# SmartRock_EC_V3_2_1_AGU.net
KiCad netlist of a schematic drawn in EAGLE
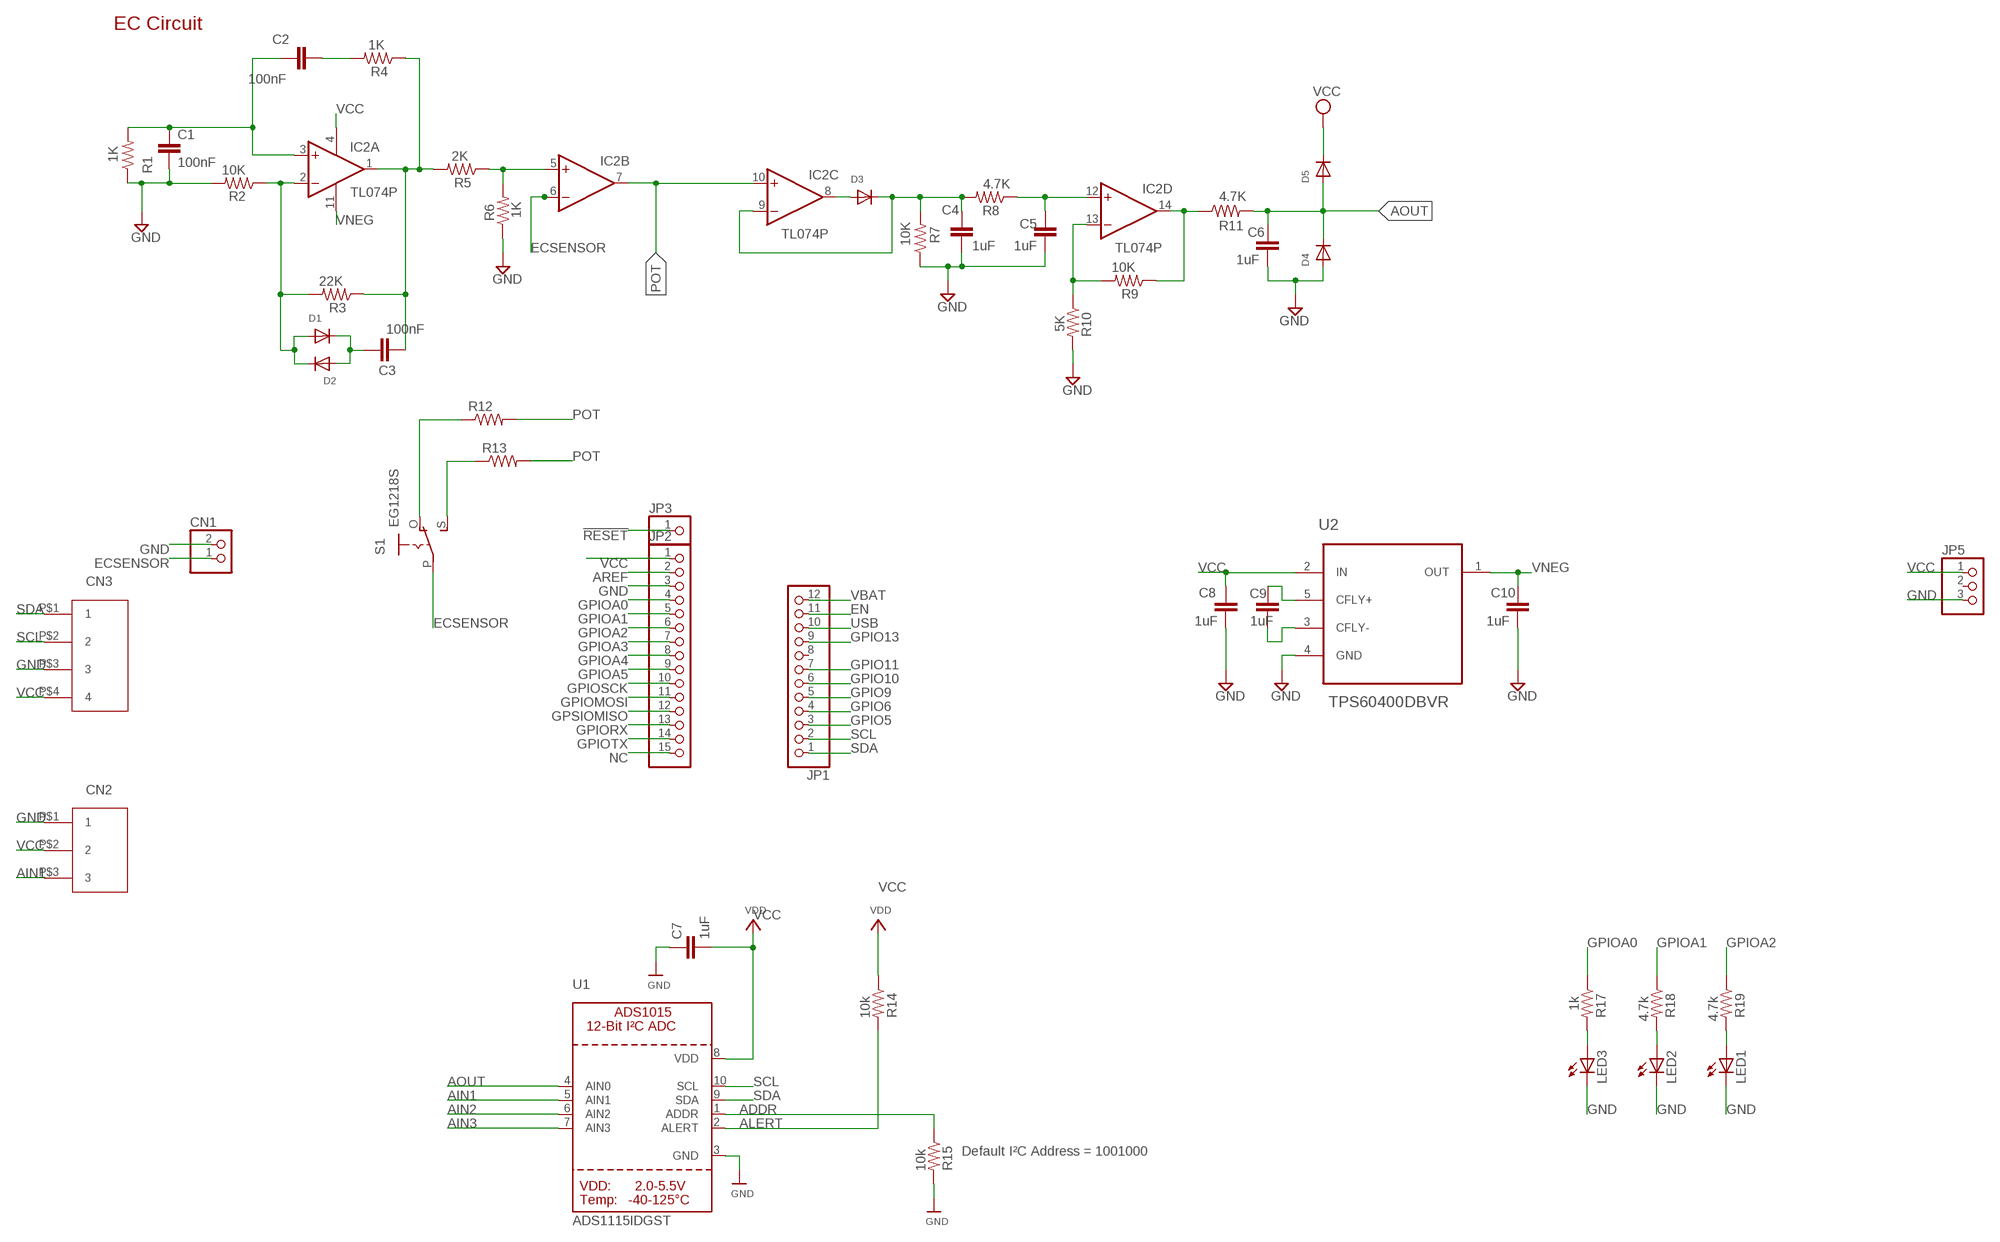
[diagram p0: schematic, sheet 1]

(export (version "E")
  (design (tool "Eeschema 10.0.6"))
  (components
    (comp (ref "C1")
      (value "100nF")
      (footprint "eagle-import:C1206")
      (libsource (lib "eagle-import") (part "C-EUC1206"))
    )
    (comp (ref "C2")
      (value "100nF")
      (footprint "eagle-import:C1206")
      (libsource (lib "eagle-import") (part "C-EUC1206"))
    )
    (comp (ref "C3")
      (value "100nF")
      (footprint "eagle-import:C1206")
      (libsource (lib "eagle-import") (part "C-EUC1206"))
    )
    (comp (ref "C4")
      (value "1uF")
      (footprint "eagle-import:C1206")
      (libsource (lib "eagle-import") (part "C-EUC1206"))
    )
    (comp (ref "C5")
      (value "1uF")
      (footprint "eagle-import:C1206")
      (libsource (lib "eagle-import") (part "C-EUC1206"))
    )
    (comp (ref "C6")
      (value "1uF")
      (footprint "eagle-import:C1206")
      (libsource (lib "eagle-import") (part "C-EUC1206"))
    )
    (comp (ref "C7")
      (value "1uF")
      (footprint "eagle-import:C1206")
      (libsource (lib "eagle-import") (part "C-EUC1206"))
    )
    (comp (ref "C8")
      (value "1uF")
      (footprint "eagle-import:C1206")
      (libsource (lib "eagle-import") (part "C-EUC1206"))
    )
    (comp (ref "C9")
      (value "1uF")
      (footprint "eagle-import:C1206")
      (libsource (lib "eagle-import") (part "C-EUC1206"))
    )
    (comp (ref "C10")
      (value "1uF")
      (footprint "eagle-import:C1206")
      (libsource (lib "eagle-import") (part "C-EUC1206"))
    )
    (comp (ref "CN1")
      (value "JST_2PIN-THM")
      (footprint "eagle-import:JST-PH-2-THM")
      (libsource (lib "eagle-import") (part "JST_2PIN-THM"))
    )
    (comp (ref "D1")
      (value "DIODEDO-1N4148")
      (footprint "eagle-import:DO-1N4148")
      (libsource (lib "eagle-import") (part "DIODEDO-1N4148"))
    )
    (comp (ref "D2")
      (value "DIODEDO-1N4148")
      (footprint "eagle-import:DO-1N4148")
      (libsource (lib "eagle-import") (part "DIODEDO-1N4148"))
    )
    (comp (ref "D3")
      (value "DIODEDO-1N4148")
      (footprint "eagle-import:DO-1N4148")
      (libsource (lib "eagle-import") (part "DIODEDO-1N4148"))
    )
    (comp (ref "D4")
      (value "DIODEDO-1N4148")
      (footprint "eagle-import:DO-1N4148")
      (libsource (lib "eagle-import") (part "DIODEDO-1N4148"))
    )
    (comp (ref "D5")
      (value "DIODEDO-1N4148")
      (footprint "eagle-import:DO-1N4148")
      (libsource (lib "eagle-import") (part "DIODEDO-1N4148"))
    )
    (comp (ref "IC2")
      (value "TL074P")
      (footprint "eagle-import:DIL14")
      (libsource (lib "eagle-import") (part "TL074P"))
    )
    (comp (ref "JP1")
      (value "PINHD-1X12-CB")
      (footprint "eagle-import:1X12-CB")
      (libsource (lib "eagle-import") (part "PINHD-1X12-CB"))
    )
    (comp (ref "JP2")
      (value "PINHD-1X15-CB")
      (footprint "eagle-import:1X15-CB")
      (libsource (lib "eagle-import") (part "PINHD-1X15-CB"))
    )
    (comp (ref "JP3")
      (value "PINHD-1X1CB")
      (footprint "eagle-import:1X01-CLEANBIG")
      (libsource (lib "eagle-import") (part "PINHD-1X1CB"))
    )
    (comp (ref "JP5")
      (value "PINHD-1X3CB")
      (footprint "eagle-import:1X03-CLEANBIG")
      (libsource (lib "eagle-import") (part "PINHD-1X3CB"))
    )
    (comp (ref "LED1")
      (value "LEDSMT1206")
      (footprint "eagle-import:1206")
      (libsource (lib "eagle-import") (part "LEDSMT1206"))
    )
    (comp (ref "LED2")
      (value "LEDSMT1206")
      (footprint "eagle-import:1206")
      (libsource (lib "eagle-import") (part "LEDSMT1206"))
    )
    (comp (ref "LED3")
      (value "LEDSMT1206")
      (footprint "eagle-import:1206")
      (libsource (lib "eagle-import") (part "LEDSMT1206"))
    )
    (comp (ref "R1")
      (value "1K")
      (footprint "eagle-import:R1206")
      (libsource (lib "eagle-import") (part "rcl_334_R-US_R1206"))
    )
    (comp (ref "R2")
      (value "10K")
      (footprint "eagle-import:R1206")
      (libsource (lib "eagle-import") (part "rcl_334_R-US_R1206"))
    )
    (comp (ref "R3")
      (value "22K")
      (footprint "eagle-import:R1206")
      (libsource (lib "eagle-import") (part "rcl_334_R-US_R1206"))
    )
    (comp (ref "R4")
      (value "1K")
      (footprint "eagle-import:R1206")
      (libsource (lib "eagle-import") (part "rcl_334_R-US_R1206"))
    )
    (comp (ref "R5")
      (value "2K")
      (footprint "eagle-import:R1206")
      (libsource (lib "eagle-import") (part "rcl_334_R-US_R1206"))
    )
    (comp (ref "R6")
      (value "1K")
      (footprint "eagle-import:R1206")
      (libsource (lib "eagle-import") (part "rcl_334_R-US_R1206"))
    )
    (comp (ref "R7")
      (value "10K")
      (footprint "eagle-import:R1206")
      (libsource (lib "eagle-import") (part "rcl_334_R-US_R1206"))
    )
    (comp (ref "R8")
      (value "4.7K")
      (footprint "eagle-import:R1206")
      (libsource (lib "eagle-import") (part "rcl_334_R-US_R1206"))
    )
    (comp (ref "R9")
      (value "10K")
      (footprint "eagle-import:R1206")
      (libsource (lib "eagle-import") (part "rcl_334_R-US_R1206"))
    )
    (comp (ref "R10")
      (value "5K")
      (footprint "eagle-import:R1206")
      (libsource (lib "eagle-import") (part "rcl_334_R-US_R1206"))
    )
    (comp (ref "R11")
      (value "4.7K")
      (footprint "eagle-import:R1206")
      (libsource (lib "eagle-import") (part "rcl_334_R-US_R1206"))
    )
    (comp (ref "R12")
      (value "R-US_0204/7")
      (footprint "eagle-import:0204_7")
      (libsource (lib "eagle-import") (part "R-US_0204/7"))
    )
    (comp (ref "R13")
      (value "R-US_0204/7")
      (footprint "eagle-import:0204_7")
      (libsource (lib "eagle-import") (part "R-US_0204/7"))
    )
    (comp (ref "R14")
      (value "10k")
      (footprint "eagle-import:R1206")
      (libsource (lib "eagle-import") (part "rcl_334_R-US_R1206"))
    )
    (comp (ref "R15")
      (value "10k")
      (footprint "eagle-import:R1206")
      (libsource (lib "eagle-import") (part "rcl_334_R-US_R1206"))
    )
    (comp (ref "R17")
      (value "1k")
      (footprint "eagle-import:R1206")
      (libsource (lib "eagle-import") (part "rcl_334_R-US_R1206"))
    )
    (comp (ref "R18")
      (value "4.7k")
      (footprint "eagle-import:R1206")
      (libsource (lib "eagle-import") (part "rcl_334_R-US_R1206"))
    )
    (comp (ref "R19")
      (value "4.7k")
      (footprint "eagle-import:R1206")
      (libsource (lib "eagle-import") (part "rcl_334_R-US_R1206"))
    )
    (comp (ref "S1")
      (value "EG1218S")
      (footprint "eagle-import:EG1218")
      (fields
        (field (name "DIGI-KEY_PART_NUMBER") "EG1218A-ND")
        (field (name "MF") "E-Switch")
        (field (name "MP") "EG1218")
      )
      (libsource (lib "eagle-import") (part "EG1218S"))
    )
    (comp (ref "U$7")
      (value "JST_4PIN_2MM")
      (footprint "eagle-import:JST_4PIN_2MM")
      (libsource (lib "eagle-import") (part "JST_4PIN_2MM"))
    )
    (comp (ref "U$9")
      (value "JST_3PIN_2MM")
      (footprint "eagle-import:JST_3PIN_2MM")
      (libsource (lib "eagle-import") (part "JST_3PIN_2MM"))
    )
    (comp (ref "U1")
      (value "ADS1115IDGST")
      (footprint "eagle-import:MSOP10")
      (libsource (lib "eagle-import") (part "ADC_ADS1015"))
    )
    (comp (ref "U2")
      (value "TPS60400DBVR")
      (footprint "eagle-import:SOT95P280X145-5N")
      (fields (field (name "MF") "Texas Instruments"))
      (libsource (lib "eagle-import") (part "TPS60400DBVR"))
    )
  )
  (nets
    (net (code "1") (name "/ADDR") (class "Default")
      (node (ref "R15") (pin "1") (pinfunction "1_1") (pintype "passive"))
      (node (ref "U1") (pin "1") (pinfunction "ADDR_1") (pintype "bidirectional"))
    )
    (net (code "2") (name "/AIN1") (class "Default")
      (node (ref "U$9") (pin "P$3") (pinfunction "3_P$3") (pintype "bidirectional"))
      (node (ref "U1") (pin "5") (pinfunction "AIN1_5") (pintype "bidirectional"))
    )
    (net (code "3") (name "/AIN2") (class "Default")
      (node (ref "U1") (pin "6") (pinfunction "AIN2_6") (pintype "bidirectional"))
    )
    (net (code "4") (name "/AIN3") (class "Default")
      (node (ref "U1") (pin "7") (pinfunction "AIN3_7") (pintype "bidirectional"))
    )
    (net (code "5") (name "/ALERT") (class "Default")
      (node (ref "R14") (pin "2") (pinfunction "2_2") (pintype "passive"))
      (node (ref "U1") (pin "2") (pinfunction "ALERT_2") (pintype "bidirectional"))
    )
    (net (code "6") (name "/AREF") (class "Default")
      (node (ref "JP2") (pin "2") (pinfunction "2_2") (pintype "passive"))
    )
    (net (code "7") (name "/ECSENSOR") (class "Default")
      (node (ref "CN1") (pin "1") (pinfunction "2_1") (pintype "passive"))
      (node (ref "IC2") (pin "6") (pinfunction "-IN_6") (pintype "input"))
      (node (ref "S1") (pin "P") (pinfunction "P_P") (pintype "passive"))
    )
    (net (code "8") (name "/EN") (class "Default")
      (node (ref "JP1") (pin "11") (pinfunction "11_11") (pintype "passive"))
    )
    (net (code "9") (name "/GPIO5") (class "Default")
      (node (ref "JP1") (pin "3") (pinfunction "3_3") (pintype "passive"))
    )
    (net (code "10") (name "/GPIO6") (class "Default")
      (node (ref "JP1") (pin "4") (pinfunction "4_4") (pintype "passive"))
    )
    (net (code "11") (name "/GPIO9") (class "Default")
      (node (ref "JP1") (pin "5") (pinfunction "5_5") (pintype "passive"))
    )
    (net (code "12") (name "/GPIO10") (class "Default")
      (node (ref "JP1") (pin "6") (pinfunction "6_6") (pintype "passive"))
    )
    (net (code "13") (name "/GPIO11") (class "Default")
      (node (ref "JP1") (pin "7") (pinfunction "7_7") (pintype "passive"))
    )
    (net (code "14") (name "/GPIO13") (class "Default")
      (node (ref "JP1") (pin "9") (pinfunction "9_9") (pintype "passive"))
    )
    (net (code "15") (name "/GPIOA0") (class "Default")
      (node (ref "JP2") (pin "4") (pinfunction "4_4") (pintype "passive"))
      (node (ref "R17") (pin "1") (pinfunction "1_1") (pintype "passive"))
    )
    (net (code "16") (name "/GPIOA1") (class "Default")
      (node (ref "JP2") (pin "5") (pinfunction "5_5") (pintype "passive"))
      (node (ref "R18") (pin "1") (pinfunction "1_1") (pintype "passive"))
    )
    (net (code "17") (name "/GPIOA2") (class "Default")
      (node (ref "JP2") (pin "6") (pinfunction "6_6") (pintype "passive"))
      (node (ref "R19") (pin "1") (pinfunction "1_1") (pintype "passive"))
    )
    (net (code "18") (name "/GPIOA3") (class "Default")
      (node (ref "JP2") (pin "7") (pinfunction "7_7") (pintype "passive"))
    )
    (net (code "19") (name "/GPIOA4") (class "Default")
      (node (ref "JP2") (pin "8") (pinfunction "8_8") (pintype "passive"))
    )
    (net (code "20") (name "/GPIOA5") (class "Default")
      (node (ref "JP2") (pin "9") (pinfunction "9_9") (pintype "passive"))
    )
    (net (code "21") (name "/GPIOMOSI") (class "Default")
      (node (ref "JP2") (pin "11") (pinfunction "11_11") (pintype "passive"))
    )
    (net (code "22") (name "/GPIORX") (class "Default")
      (node (ref "JP2") (pin "13") (pinfunction "13_13") (pintype "passive"))
    )
    (net (code "23") (name "/GPIOSCK") (class "Default")
      (node (ref "JP2") (pin "10") (pinfunction "10_10") (pintype "passive"))
    )
    (net (code "24") (name "/GPIOTX") (class "Default")
      (node (ref "JP2") (pin "14") (pinfunction "14_14") (pintype "passive"))
    )
    (net (code "25") (name "/GPSIOMISO") (class "Default")
      (node (ref "JP2") (pin "12") (pinfunction "12_12") (pintype "passive"))
    )
    (net (code "26") (name "/NC") (class "Default")
      (node (ref "JP2") (pin "15") (pinfunction "15_15") (pintype "passive"))
    )
    (net (code "27") (name "/SCL") (class "Default")
      (node (ref "JP1") (pin "2") (pinfunction "2_2") (pintype "passive"))
      (node (ref "U$7") (pin "P$2") (pinfunction "2_P$2") (pintype "bidirectional"))
      (node (ref "U1") (pin "10") (pinfunction "SCL_10") (pintype "bidirectional"))
    )
    (net (code "28") (name "/SDA") (class "Default")
      (node (ref "JP1") (pin "1") (pinfunction "1_1") (pintype "passive"))
      (node (ref "U$7") (pin "P$1") (pinfunction "1_P$1") (pintype "bidirectional"))
      (node (ref "U1") (pin "9") (pinfunction "SDA_9") (pintype "bidirectional"))
    )
    (net (code "29") (name "/USB") (class "Default")
      (node (ref "JP1") (pin "10") (pinfunction "10_10") (pintype "passive"))
    )
    (net (code "30") (name "/VBAT") (class "Default")
      (node (ref "JP1") (pin "12") (pinfunction "12_12") (pintype "passive"))
    )
    (net (code "31") (name "/VNEG") (class "Default")
      (node (ref "C10") (pin "2") (pinfunction "2_2") (pintype "passive"))
      (node (ref "IC2") (pin "11") (pinfunction "V-_11") (pintype "power_in"))
      (node (ref "U2") (pin "1") (pinfunction "OUT_1") (pintype "output"))
    )
    (net (code "32") (name "/~{RESET}") (class "Default")
      (node (ref "JP3") (pin "1") (pinfunction "1_1") (pintype "passive"))
    )
    (net (code "33") (name "AOUT") (class "Default")
      (node (ref "C6") (pin "2") (pinfunction "2_2") (pintype "passive"))
      (node (ref "D4") (pin "C") (pinfunction "C_C") (pintype "passive"))
      (node (ref "D5") (pin "A") (pinfunction "A_A") (pintype "passive"))
      (node (ref "R11") (pin "2") (pinfunction "2_2") (pintype "passive"))
      (node (ref "U1") (pin "4") (pinfunction "AIN0_4") (pintype "bidirectional"))
    )
    (net (code "34") (name "GND") (class "Default")
      (node (ref "C1") (pin "2") (pinfunction "2_2") (pintype "passive"))
      (node (ref "C10") (pin "1") (pinfunction "1_1") (pintype "passive"))
      (node (ref "C4") (pin "1") (pinfunction "1_1") (pintype "passive"))
      (node (ref "C5") (pin "1") (pinfunction "1_1") (pintype "passive"))
      (node (ref "C6") (pin "1") (pinfunction "1_1") (pintype "passive"))
      (node (ref "C7") (pin "1") (pinfunction "1_1") (pintype "passive"))
      (node (ref "C8") (pin "1") (pinfunction "1_1") (pintype "passive"))
      (node (ref "CN1") (pin "2") (pinfunction "1_2") (pintype "passive"))
      (node (ref "D4") (pin "A") (pinfunction "A_A") (pintype "passive"))
      (node (ref "JP2") (pin "3") (pinfunction "3_3") (pintype "passive"))
      (node (ref "JP5") (pin "3") (pinfunction "3_3") (pintype "passive"))
      (node (ref "LED1") (pin "C") (pinfunction "C_C") (pintype "passive"))
      (node (ref "LED2") (pin "C") (pinfunction "C_C") (pintype "passive"))
      (node (ref "LED3") (pin "C") (pinfunction "C_C") (pintype "passive"))
      (node (ref "R1") (pin "1") (pinfunction "1_1") (pintype "passive"))
      (node (ref "R10") (pin "2") (pinfunction "2_2") (pintype "passive"))
      (node (ref "R15") (pin "2") (pinfunction "2_2") (pintype "passive"))
      (node (ref "R2") (pin "2") (pinfunction "2_2") (pintype "passive"))
      (node (ref "R6") (pin "1") (pinfunction "1_1") (pintype "passive"))
      (node (ref "R7") (pin "1") (pinfunction "1_1") (pintype "passive"))
      (node (ref "U$7") (pin "P$3") (pinfunction "3_P$3") (pintype "bidirectional"))
      (node (ref "U$9") (pin "P$1") (pinfunction "1_P$1") (pintype "bidirectional"))
      (node (ref "U1") (pin "3") (pinfunction "GND_3") (pintype "bidirectional"))
      (node (ref "U2") (pin "4") (pinfunction "GND_4") (pintype "passive"))
    )
    (net (code "35") (name "Net-(C2-Pad2)") (class "Default")
      (node (ref "C2") (pin "2") (pinfunction "2_2") (pintype "passive"))
      (node (ref "R4") (pin "2") (pinfunction "2_2") (pintype "passive"))
    )
    (net (code "36") (name "Net-(C3-Pad1)") (class "Default")
      (node (ref "C3") (pin "1") (pinfunction "1_1") (pintype "passive"))
      (node (ref "D1") (pin "C") (pinfunction "C_C") (pintype "passive"))
      (node (ref "D2") (pin "A") (pinfunction "A_A") (pintype "passive"))
    )
    (net (code "37") (name "Net-(IC2A-+IN)") (class "Default")
      (node (ref "C1") (pin "1") (pinfunction "1_1") (pintype "passive"))
      (node (ref "C2") (pin "1") (pinfunction "1_1") (pintype "passive"))
      (node (ref "IC2") (pin "3") (pinfunction "+IN_3") (pintype "input"))
      (node (ref "R1") (pin "2") (pinfunction "2_2") (pintype "passive"))
    )
    (net (code "38") (name "Net-(IC2A--IN)") (class "Default")
      (node (ref "D1") (pin "A") (pinfunction "A_A") (pintype "passive"))
      (node (ref "D2") (pin "C") (pinfunction "C_C") (pintype "passive"))
      (node (ref "IC2") (pin "2") (pinfunction "-IN_2") (pintype "input"))
      (node (ref "R2") (pin "1") (pinfunction "1_1") (pintype "passive"))
      (node (ref "R3") (pin "2") (pinfunction "2_2") (pintype "passive"))
    )
    (net (code "39") (name "Net-(IC2A-OUT)") (class "Default")
      (node (ref "C3") (pin "2") (pinfunction "2_2") (pintype "passive"))
      (node (ref "IC2") (pin "1") (pinfunction "OUT_1") (pintype "output"))
      (node (ref "R3") (pin "1") (pinfunction "1_1") (pintype "passive"))
      (node (ref "R4") (pin "1") (pinfunction "1_1") (pintype "passive"))
      (node (ref "R5") (pin "2") (pinfunction "2_2") (pintype "passive"))
    )
    (net (code "40") (name "Net-(IC2B-+IN)") (class "Default")
      (node (ref "IC2") (pin "5") (pinfunction "+IN_5") (pintype "input"))
      (node (ref "R5") (pin "1") (pinfunction "1_1") (pintype "passive"))
      (node (ref "R6") (pin "2") (pinfunction "2_2") (pintype "passive"))
    )
    (net (code "41") (name "Net-(IC2C--IN)") (class "Default")
      (node (ref "C4") (pin "2") (pinfunction "2_2") (pintype "passive"))
      (node (ref "D3") (pin "C") (pinfunction "C_C") (pintype "passive"))
      (node (ref "IC2") (pin "9") (pinfunction "-IN_9") (pintype "input"))
      (node (ref "R7") (pin "2") (pinfunction "2_2") (pintype "passive"))
      (node (ref "R8") (pin "2") (pinfunction "2_2") (pintype "passive"))
    )
    (net (code "42") (name "Net-(IC2C-OUT)") (class "Default")
      (node (ref "D3") (pin "A") (pinfunction "A_A") (pintype "passive"))
      (node (ref "IC2") (pin "8") (pinfunction "OUT_8") (pintype "output"))
    )
    (net (code "43") (name "Net-(IC2D-+IN)") (class "Default")
      (node (ref "C5") (pin "2") (pinfunction "2_2") (pintype "passive"))
      (node (ref "IC2") (pin "12") (pinfunction "+IN_12") (pintype "input"))
      (node (ref "R8") (pin "1") (pinfunction "1_1") (pintype "passive"))
    )
    (net (code "44") (name "Net-(IC2D--IN)") (class "Default")
      (node (ref "IC2") (pin "13") (pinfunction "-IN_13") (pintype "input"))
      (node (ref "R10") (pin "1") (pinfunction "1_1") (pintype "passive"))
      (node (ref "R9") (pin "2") (pinfunction "2_2") (pintype "passive"))
    )
    (net (code "45") (name "Net-(IC2D-OUT)") (class "Default")
      (node (ref "IC2") (pin "14") (pinfunction "OUT_14") (pintype "output"))
      (node (ref "R11") (pin "1") (pinfunction "1_1") (pintype "passive"))
      (node (ref "R9") (pin "1") (pinfunction "1_1") (pintype "passive"))
    )
    (net (code "46") (name "Net-(LED1-PadA)") (class "Default")
      (node (ref "LED1") (pin "A") (pinfunction "A_A") (pintype "passive"))
      (node (ref "R19") (pin "2") (pinfunction "2_2") (pintype "passive"))
    )
    (net (code "47") (name "Net-(LED2-PadA)") (class "Default")
      (node (ref "LED2") (pin "A") (pinfunction "A_A") (pintype "passive"))
      (node (ref "R18") (pin "2") (pinfunction "2_2") (pintype "passive"))
    )
    (net (code "48") (name "Net-(LED3-PadA)") (class "Default")
      (node (ref "LED3") (pin "A") (pinfunction "A_A") (pintype "passive"))
      (node (ref "R17") (pin "2") (pinfunction "2_2") (pintype "passive"))
    )
    (net (code "49") (name "Net-(R12-Pad1)") (class "Default")
      (node (ref "R12") (pin "1") (pinfunction "1_1") (pintype "passive"))
      (node (ref "S1") (pin "O") (pinfunction "O_O") (pintype "passive"))
    )
    (net (code "50") (name "Net-(R13-Pad1)") (class "Default")
      (node (ref "R13") (pin "1") (pinfunction "1_1") (pintype "passive"))
      (node (ref "S1") (pin "S") (pinfunction "S_S") (pintype "passive"))
    )
    (net (code "51") (name "Net-(U2-CFLY+)") (class "Default")
      (node (ref "C9") (pin "2") (pinfunction "2_2") (pintype "passive"))
      (node (ref "U2") (pin "5") (pinfunction "CFLY+_5") (pintype "input"))
    )
    (net (code "52") (name "Net-(U2-CFLY-)") (class "Default")
      (node (ref "C9") (pin "1") (pinfunction "1_1") (pintype "passive"))
      (node (ref "U2") (pin "3") (pinfunction "CFLY-_3") (pintype "input"))
    )
    (net (code "53") (name "POT") (class "Default")
      (node (ref "IC2") (pin "10") (pinfunction "+IN_10") (pintype "input"))
      (node (ref "IC2") (pin "7") (pinfunction "OUT_7") (pintype "output"))
      (node (ref "R12") (pin "2") (pinfunction "2_2") (pintype "passive"))
      (node (ref "R13") (pin "2") (pinfunction "2_2") (pintype "passive"))
    )
    (net (code "54") (name "VCC") (class "Default")
      (node (ref "C7") (pin "2") (pinfunction "2_2") (pintype "passive"))
      (node (ref "C8") (pin "2") (pinfunction "2_2") (pintype "passive"))
      (node (ref "D5") (pin "C") (pinfunction "C_C") (pintype "passive"))
      (node (ref "IC2") (pin "4") (pinfunction "V+_4") (pintype "power_in"))
      (node (ref "JP2") (pin "1") (pinfunction "1_1") (pintype "passive"))
      (node (ref "JP5") (pin "1") (pinfunction "1_1") (pintype "passive"))
      (node (ref "R14") (pin "1") (pinfunction "1_1") (pintype "passive"))
      (node (ref "U$7") (pin "P$4") (pinfunction "4_P$4") (pintype "bidirectional"))
      (node (ref "U$9") (pin "P$2") (pinfunction "2_P$2") (pintype "bidirectional"))
      (node (ref "U1") (pin "8") (pinfunction "VDD_8") (pintype "bidirectional"))
      (node (ref "U2") (pin "2") (pinfunction "IN_2") (pintype "power_in"))
    )
    (net (code "55") (name "unconnected-(JP1-Pad8)") (class "Default")
      (node (ref "JP1") (pin "8") (pinfunction "8_8") (pintype "passive"))
    )
    (net (code "56") (name "unconnected-(JP5-Pad2)") (class "Default")
      (node (ref "JP5") (pin "2") (pinfunction "2_2") (pintype "passive"))
    )
  )
)
